# SensorInt.net
KiCad netlist of a schematic drawn in Altium Designer
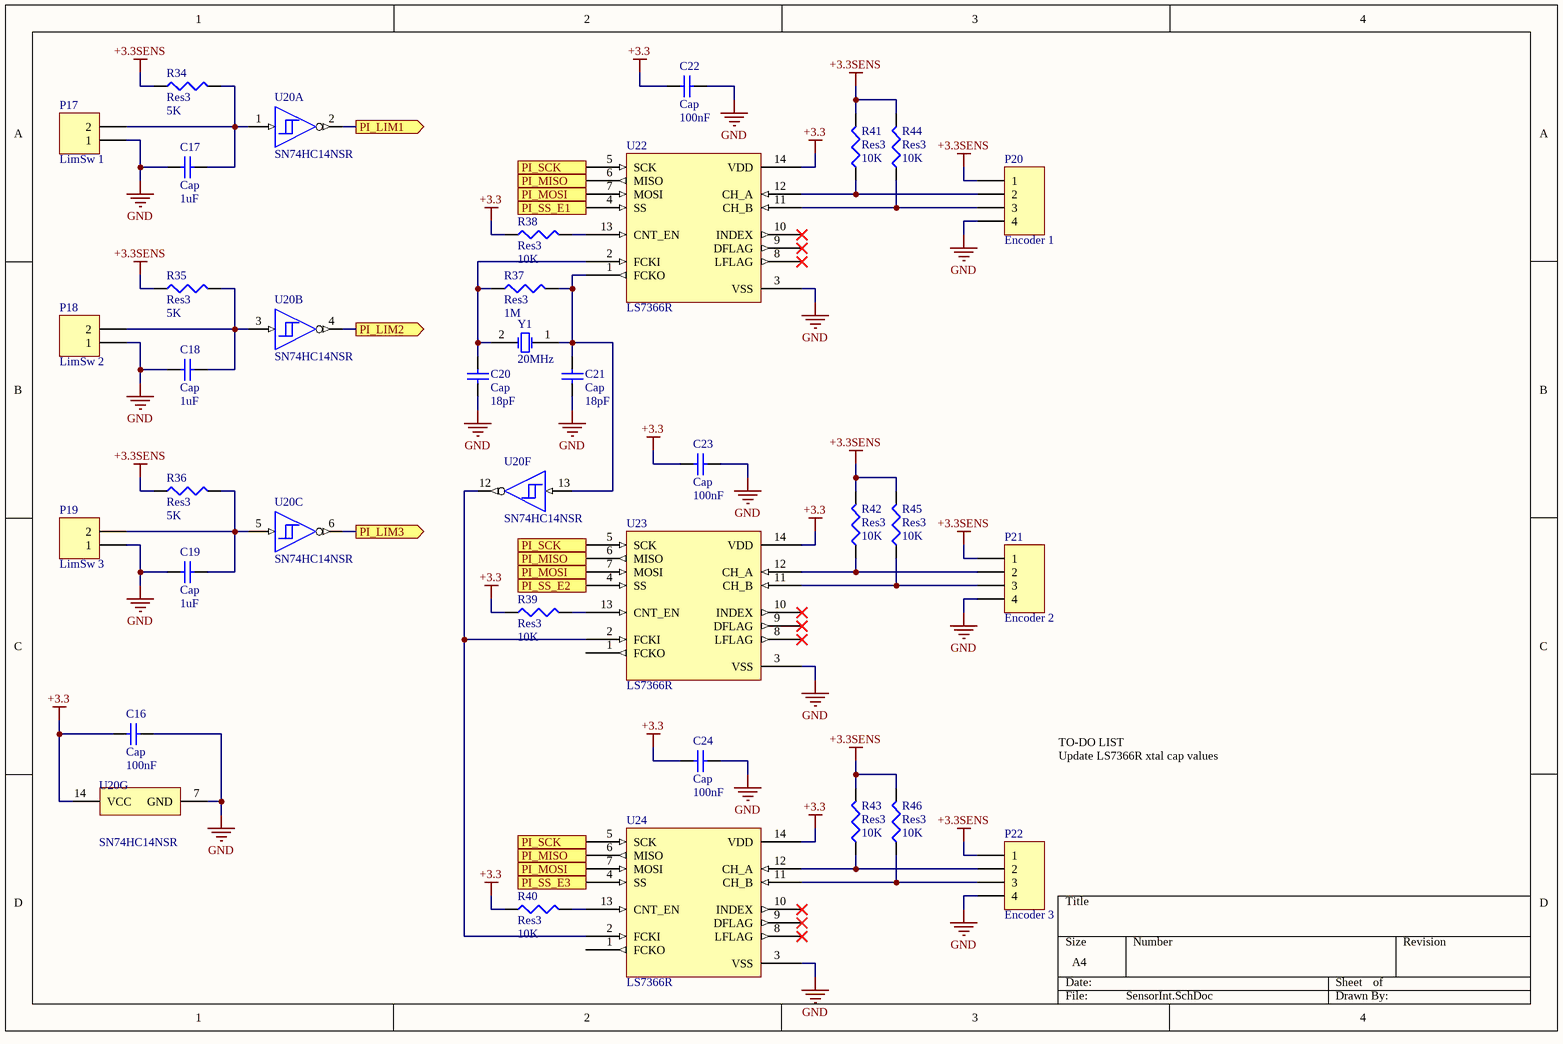
[diagram p0: SensorInt.SchDoc]

(export (version "E")
  (design (tool "Eeschema 10.0.6"))
  (components
    (comp (ref "C16")
      (value "Cap")
      (footprint "C0805")
      (description "Capacitor")
      (fields (field (name "ALTIUM_VALUE") "100nF") (field (name "PUBLISHER") "Altium Limited"))
      (libsource (lib "Miscellaneous Devices") (part "Cap"))
    )
    (comp (ref "C17")
      (value "Cap")
      (footprint "C0805")
      (description "Capacitor")
      (fields (field (name "ALTIUM_VALUE") "1uF") (field (name "PUBLISHER") "Altium Limited"))
      (libsource (lib "Miscellaneous Devices") (part "Cap"))
    )
    (comp (ref "C18")
      (value "Cap")
      (footprint "C0805")
      (description "Capacitor")
      (fields (field (name "ALTIUM_VALUE") "1uF") (field (name "PUBLISHER") "Altium Limited"))
      (libsource (lib "Miscellaneous Devices") (part "Cap"))
    )
    (comp (ref "C19")
      (value "Cap")
      (footprint "C0805")
      (description "Capacitor")
      (fields (field (name "ALTIUM_VALUE") "1uF") (field (name "PUBLISHER") "Altium Limited"))
      (libsource (lib "Miscellaneous Devices") (part "Cap"))
    )
    (comp (ref "C20")
      (value "Cap")
      (footprint "C0805")
      (description "Capacitor")
      (fields (field (name "ALTIUM_VALUE") "18pF") (field (name "PUBLISHER") "Altium Limited"))
      (libsource (lib "Miscellaneous Devices") (part "Cap"))
    )
    (comp (ref "C21")
      (value "Cap")
      (footprint "C0805")
      (description "Capacitor")
      (fields (field (name "ALTIUM_VALUE") "18pF") (field (name "PUBLISHER") "Altium Limited"))
      (libsource (lib "Miscellaneous Devices") (part "Cap"))
    )
    (comp (ref "C22")
      (value "Cap")
      (footprint "C0805")
      (description "Capacitor")
      (fields (field (name "ALTIUM_VALUE") "100nF") (field (name "PUBLISHER") "Altium Limited"))
      (libsource (lib "Miscellaneous Devices") (part "Cap"))
    )
    (comp (ref "C23")
      (value "Cap")
      (footprint "C0805")
      (description "Capacitor")
      (fields (field (name "ALTIUM_VALUE") "100nF") (field (name "PUBLISHER") "Altium Limited"))
      (libsource (lib "Miscellaneous Devices") (part "Cap"))
    )
    (comp (ref "C24")
      (value "Cap")
      (footprint "C0805")
      (description "Capacitor")
      (fields (field (name "ALTIUM_VALUE") "100nF") (field (name "PUBLISHER") "Altium Limited"))
      (libsource (lib "Miscellaneous Devices") (part "Cap"))
    )
    (comp (ref "P17")
      (value "LimSw 1")
      (footprint "22-23-20x1-2pos")
      (description "Header, 2-Pin")
      (fields (field (name "PUBLISHER") "Altium Limited"))
      (libsource (lib "Miscellaneous Connectors") (part "Header 2"))
    )
    (comp (ref "P18")
      (value "LimSw 2")
      (footprint "22-23-20x1-2pos")
      (description "Header, 2-Pin")
      (fields (field (name "PUBLISHER") "Altium Limited"))
      (libsource (lib "Miscellaneous Connectors") (part "Header 2"))
    )
    (comp (ref "P19")
      (value "LimSw 3")
      (footprint "22-23-20x1-2pos")
      (description "Header, 2-Pin")
      (fields (field (name "PUBLISHER") "Altium Limited"))
      (libsource (lib "Miscellaneous Connectors") (part "Header 2"))
    )
    (comp (ref "P20")
      (value "Encoder 1")
      (footprint "22-23-20x1-4pos")
      (description "Header, 4-Pin")
      (fields (field (name "PUBLISHER") "Altium Limited"))
      (libsource (lib "Miscellaneous Connectors") (part "Header 4"))
    )
    (comp (ref "P21")
      (value "Encoder 2")
      (footprint "22-23-20x1-4pos")
      (description "Header, 4-Pin")
      (fields (field (name "PUBLISHER") "Altium Limited"))
      (libsource (lib "Miscellaneous Connectors") (part "Header 4"))
    )
    (comp (ref "P22")
      (value "Encoder 3")
      (footprint "22-23-20x1-4pos")
      (description "Header, 4-Pin")
      (fields (field (name "PUBLISHER") "Altium Limited"))
      (libsource (lib "Miscellaneous Connectors") (part "Header 4"))
    )
    (comp (ref "R34")
      (value "Res3")
      (footprint "C0805")
      (description "Resistor")
      (fields (field (name "ALTIUM_VALUE") "5K") (field (name "PUBLISHER") "Altium Limited"))
      (libsource (lib "Miscellaneous Devices") (part "Res3"))
    )
    (comp (ref "R35")
      (value "Res3")
      (footprint "C0805")
      (description "Resistor")
      (fields (field (name "ALTIUM_VALUE") "5K") (field (name "PUBLISHER") "Altium Limited"))
      (libsource (lib "Miscellaneous Devices") (part "Res3"))
    )
    (comp (ref "R36")
      (value "Res3")
      (footprint "C0805")
      (description "Resistor")
      (fields (field (name "ALTIUM_VALUE") "5K") (field (name "PUBLISHER") "Altium Limited"))
      (libsource (lib "Miscellaneous Devices") (part "Res3"))
    )
    (comp (ref "R37")
      (value "Res3")
      (footprint "C0805")
      (description "Resistor")
      (fields (field (name "ALTIUM_VALUE") "1M") (field (name "PUBLISHER") "Altium Limited"))
      (libsource (lib "Miscellaneous Devices") (part "Res3"))
    )
    (comp (ref "R38")
      (value "Res3")
      (footprint "C0805")
      (description "Resistor")
      (fields (field (name "ALTIUM_VALUE") "10K") (field (name "PUBLISHER") "Altium Limited"))
      (libsource (lib "Miscellaneous Devices") (part "Res3"))
    )
    (comp (ref "R39")
      (value "Res3")
      (footprint "C0805")
      (description "Resistor")
      (fields (field (name "ALTIUM_VALUE") "10K") (field (name "PUBLISHER") "Altium Limited"))
      (libsource (lib "Miscellaneous Devices") (part "Res3"))
    )
    (comp (ref "R40")
      (value "Res3")
      (footprint "C0805")
      (description "Resistor")
      (fields (field (name "ALTIUM_VALUE") "10K") (field (name "PUBLISHER") "Altium Limited"))
      (libsource (lib "Miscellaneous Devices") (part "Res3"))
    )
    (comp (ref "R41")
      (value "Res3")
      (footprint "C0805")
      (description "Resistor")
      (fields (field (name "ALTIUM_VALUE") "10K") (field (name "PUBLISHER") "Altium Limited"))
      (libsource (lib "Miscellaneous Devices") (part "Res3"))
    )
    (comp (ref "R42")
      (value "Res3")
      (footprint "C0805")
      (description "Resistor")
      (fields (field (name "ALTIUM_VALUE") "10K") (field (name "PUBLISHER") "Altium Limited"))
      (libsource (lib "Miscellaneous Devices") (part "Res3"))
    )
    (comp (ref "R43")
      (value "Res3")
      (footprint "C0805")
      (description "Resistor")
      (fields (field (name "ALTIUM_VALUE") "10K") (field (name "PUBLISHER") "Altium Limited"))
      (libsource (lib "Miscellaneous Devices") (part "Res3"))
    )
    (comp (ref "R44")
      (value "Res3")
      (footprint "C0805")
      (description "Resistor")
      (fields (field (name "ALTIUM_VALUE") "10K") (field (name "PUBLISHER") "Altium Limited"))
      (libsource (lib "Miscellaneous Devices") (part "Res3"))
    )
    (comp (ref "R45")
      (value "Res3")
      (footprint "C0805")
      (description "Resistor")
      (fields (field (name "ALTIUM_VALUE") "10K") (field (name "PUBLISHER") "Altium Limited"))
      (libsource (lib "Miscellaneous Devices") (part "Res3"))
    )
    (comp (ref "R46")
      (value "Res3")
      (footprint "C0805")
      (description "Resistor")
      (fields (field (name "ALTIUM_VALUE") "10K") (field (name "PUBLISHER") "Altium Limited"))
      (libsource (lib "Miscellaneous Devices") (part "Res3"))
    )
    (comp (ref "U20")
      (value "SN74HC14NSR")
      (footprint "NS0014A_M")
      (description "Hex Schmitt-Trigger Inverters, NS0014A, LARGE T&R")
      (fields
        (field (name "GENERIC PART NUMBER") "SN74HC14")
        (field (name "MANUFACTURER") "Texas Instruments")
      )
      (libsource (lib "Altium Content Vault") (part "TI-CD_SNX4XXXXXX4X_19A-14-SCHMITT"))
    )
    (comp (ref "U22")
      (value "LS7366R")
      (footprint "SOIC14N")
      (description "32-BIT QUADRATURE COUNTER WITH SERIAL INTERFACE")
      (libsource (lib "ScienceSymbols") (part "LS7366R"))
    )
    (comp (ref "U23")
      (value "LS7366R")
      (footprint "SOIC14N")
      (description "32-BIT QUADRATURE COUNTER WITH SERIAL INTERFACE")
      (libsource (lib "ScienceSymbols") (part "LS7366R"))
    )
    (comp (ref "U24")
      (value "LS7366R")
      (footprint "SOIC14N")
      (description "32-BIT QUADRATURE COUNTER WITH SERIAL INTERFACE")
      (libsource (lib "ScienceSymbols") (part "LS7366R"))
    )
    (comp (ref "Y1")
      (value "20MHz")
      (footprint "ABM3")
      (description "Crystal Oscillator")
      (fields (field (name "PUBLISHER") "Altium Limited"))
      (libsource (lib "Miscellaneous Devices") (part "XTAL"))
    )
  )
  (nets
    (net (code "1") (name "+3.3") (class "Default")
      (node (ref "C16") (pin "1") (pinfunction "1_1") (pintype "passive"))
      (node (ref "C22") (pin "1") (pinfunction "1_1") (pintype "passive"))
      (node (ref "C23") (pin "1") (pinfunction "1_1") (pintype "passive"))
      (node (ref "C24") (pin "1") (pinfunction "1_1") (pintype "passive"))
      (node (ref "R38") (pin "1") (pinfunction "1_1") (pintype "passive"))
      (node (ref "R39") (pin "1") (pinfunction "1_1") (pintype "passive"))
      (node (ref "R40") (pin "1") (pinfunction "1_1") (pintype "passive"))
      (node (ref "U20") (pin "14") (pinfunction "VCC_14") (pintype "power_in"))
      (node (ref "U22") (pin "14") (pinfunction "VDD_14") (pintype "power_in"))
      (node (ref "U23") (pin "14") (pinfunction "VDD_14") (pintype "power_in"))
      (node (ref "U24") (pin "14") (pinfunction "VDD_14") (pintype "power_in"))
    )
    (net (code "2") (name "+3.3SENS") (class "Default")
      (node (ref "P20") (pin "1") (pinfunction "1_1") (pintype "passive"))
      (node (ref "P21") (pin "1") (pinfunction "1_1") (pintype "passive"))
      (node (ref "P22") (pin "1") (pinfunction "1_1") (pintype "passive"))
      (node (ref "R34") (pin "1") (pinfunction "1_1") (pintype "passive"))
      (node (ref "R35") (pin "1") (pinfunction "1_1") (pintype "passive"))
      (node (ref "R36") (pin "1") (pinfunction "1_1") (pintype "passive"))
      (node (ref "R41") (pin "2") (pinfunction "2_2") (pintype "passive"))
      (node (ref "R42") (pin "2") (pinfunction "2_2") (pintype "passive"))
      (node (ref "R43") (pin "2") (pinfunction "2_2") (pintype "passive"))
      (node (ref "R44") (pin "2") (pinfunction "2_2") (pintype "passive"))
      (node (ref "R45") (pin "2") (pinfunction "2_2") (pintype "passive"))
      (node (ref "R46") (pin "2") (pinfunction "2_2") (pintype "passive"))
    )
    (net (code "3") (name "/PI_LIM1") (class "Default")
      (node (ref "U20") (pin "2") (pinfunction "~{1Y}_2") (pintype "output"))
    )
    (net (code "4") (name "/PI_LIM2") (class "Default")
      (node (ref "U20") (pin "4") (pinfunction "~{2Y}_4") (pintype "output"))
    )
    (net (code "5") (name "/PI_LIM3") (class "Default")
      (node (ref "U20") (pin "6") (pinfunction "~{3Y}_6") (pintype "output"))
    )
    (net (code "6") (name "/PI_MISO") (class "Default")
      (node (ref "U22") (pin "6") (pinfunction "MISO_6") (pintype "output"))
      (node (ref "U23") (pin "6") (pinfunction "MISO_6") (pintype "output"))
      (node (ref "U24") (pin "6") (pinfunction "MISO_6") (pintype "output"))
    )
    (net (code "7") (name "/PI_MOSI") (class "Default")
      (node (ref "U22") (pin "7") (pinfunction "MOSI_7") (pintype "input"))
      (node (ref "U23") (pin "7") (pinfunction "MOSI_7") (pintype "input"))
      (node (ref "U24") (pin "7") (pinfunction "MOSI_7") (pintype "input"))
    )
    (net (code "8") (name "/PI_SCK") (class "Default")
      (node (ref "U22") (pin "5") (pinfunction "SCK_5") (pintype "input"))
      (node (ref "U23") (pin "5") (pinfunction "SCK_5") (pintype "input"))
      (node (ref "U24") (pin "5") (pinfunction "SCK_5") (pintype "input"))
    )
    (net (code "9") (name "/PI_SS_E1") (class "Default")
      (node (ref "U22") (pin "4") (pinfunction "SS_4") (pintype "input"))
    )
    (net (code "10") (name "/PI_SS_E2") (class "Default")
      (node (ref "U23") (pin "4") (pinfunction "SS_4") (pintype "input"))
    )
    (net (code "11") (name "/PI_SS_E3") (class "Default")
      (node (ref "U24") (pin "4") (pinfunction "SS_4") (pintype "input"))
    )
    (net (code "12") (name "GND") (class "Default")
      (node (ref "C16") (pin "2") (pinfunction "2_2") (pintype "passive"))
      (node (ref "C17") (pin "1") (pinfunction "1_1") (pintype "passive"))
      (node (ref "C18") (pin "1") (pinfunction "1_1") (pintype "passive"))
      (node (ref "C19") (pin "1") (pinfunction "1_1") (pintype "passive"))
      (node (ref "C20") (pin "1") (pinfunction "1_1") (pintype "passive"))
      (node (ref "C21") (pin "1") (pinfunction "1_1") (pintype "passive"))
      (node (ref "C22") (pin "2") (pinfunction "2_2") (pintype "passive"))
      (node (ref "C23") (pin "2") (pinfunction "2_2") (pintype "passive"))
      (node (ref "C24") (pin "2") (pinfunction "2_2") (pintype "passive"))
      (node (ref "P17") (pin "1") (pinfunction "1_1") (pintype "passive"))
      (node (ref "P18") (pin "1") (pinfunction "1_1") (pintype "passive"))
      (node (ref "P19") (pin "1") (pinfunction "1_1") (pintype "passive"))
      (node (ref "P20") (pin "4") (pinfunction "4_4") (pintype "passive"))
      (node (ref "P21") (pin "4") (pinfunction "4_4") (pintype "passive"))
      (node (ref "P22") (pin "4") (pinfunction "4_4") (pintype "passive"))
      (node (ref "U20") (pin "7") (pinfunction "GND_7") (pintype "power_in"))
      (node (ref "U22") (pin "3") (pinfunction "VSS_3") (pintype "power_in"))
      (node (ref "U23") (pin "3") (pinfunction "VSS_3") (pintype "power_in"))
      (node (ref "U24") (pin "3") (pinfunction "VSS_3") (pintype "power_in"))
    )
    (net (code "13") (name "Net-(U20A-1A)") (class "Default")
      (node (ref "C17") (pin "2") (pinfunction "2_2") (pintype "passive"))
      (node (ref "P17") (pin "2") (pinfunction "2_2") (pintype "passive"))
      (node (ref "R34") (pin "2") (pinfunction "2_2") (pintype "passive"))
      (node (ref "U20") (pin "1") (pinfunction "1A_1") (pintype "input"))
    )
    (net (code "14") (name "Net-(U20B-2A)") (class "Default")
      (node (ref "C18") (pin "2") (pinfunction "2_2") (pintype "passive"))
      (node (ref "P18") (pin "2") (pinfunction "2_2") (pintype "passive"))
      (node (ref "R35") (pin "2") (pinfunction "2_2") (pintype "passive"))
      (node (ref "U20") (pin "3") (pinfunction "2A_3") (pintype "input"))
    )
    (net (code "15") (name "Net-(U20C-3A)") (class "Default")
      (node (ref "C19") (pin "2") (pinfunction "2_2") (pintype "passive"))
      (node (ref "P19") (pin "2") (pinfunction "2_2") (pintype "passive"))
      (node (ref "R36") (pin "2") (pinfunction "2_2") (pintype "passive"))
      (node (ref "U20") (pin "5") (pinfunction "3A_5") (pintype "input"))
    )
    (net (code "16") (name "Net-(U20F-6A)") (class "Default")
      (node (ref "C21") (pin "2") (pinfunction "2_2") (pintype "passive"))
      (node (ref "R37") (pin "2") (pinfunction "2_2") (pintype "passive"))
      (node (ref "U20") (pin "13") (pinfunction "6A_13") (pintype "input"))
      (node (ref "U22") (pin "1") (pinfunction "FCKO_1") (pintype "output"))
      (node (ref "Y1") (pin "1") (pinfunction "OSC1_1") (pintype "passive"))
    )
    (net (code "17") (name "Net-(U20F-~{6Y})") (class "Default")
      (node (ref "U20") (pin "12") (pinfunction "~{6Y}_12") (pintype "output"))
      (node (ref "U23") (pin "2") (pinfunction "FCKI_2") (pintype "input"))
      (node (ref "U24") (pin "2") (pinfunction "FCKI_2") (pintype "input"))
    )
    (net (code "18") (name "Net-(U22-CH_A)") (class "Default")
      (node (ref "P20") (pin "2") (pinfunction "2_2") (pintype "passive"))
      (node (ref "R41") (pin "1") (pinfunction "1_1") (pintype "passive"))
      (node (ref "U22") (pin "12") (pinfunction "CH_A_12") (pintype "input"))
    )
    (net (code "19") (name "Net-(U22-CH_B)") (class "Default")
      (node (ref "P20") (pin "3") (pinfunction "3_3") (pintype "passive"))
      (node (ref "R44") (pin "1") (pinfunction "1_1") (pintype "passive"))
      (node (ref "U22") (pin "11") (pinfunction "CH_B_11") (pintype "input"))
    )
    (net (code "20") (name "Net-(U22-CNT_EN)") (class "Default")
      (node (ref "R38") (pin "2") (pinfunction "2_2") (pintype "passive"))
      (node (ref "U22") (pin "13") (pinfunction "CNT_EN_13") (pintype "input"))
    )
    (net (code "21") (name "Net-(U22-FCKI)") (class "Default")
      (node (ref "C20") (pin "2") (pinfunction "2_2") (pintype "passive"))
      (node (ref "R37") (pin "1") (pinfunction "1_1") (pintype "passive"))
      (node (ref "U22") (pin "2") (pinfunction "FCKI_2") (pintype "input"))
      (node (ref "Y1") (pin "2") (pinfunction "OSC2_2") (pintype "passive"))
    )
    (net (code "22") (name "Net-(U23-CH_A)") (class "Default")
      (node (ref "P21") (pin "2") (pinfunction "2_2") (pintype "passive"))
      (node (ref "R42") (pin "1") (pinfunction "1_1") (pintype "passive"))
      (node (ref "U23") (pin "12") (pinfunction "CH_A_12") (pintype "input"))
    )
    (net (code "23") (name "Net-(U23-CH_B)") (class "Default")
      (node (ref "P21") (pin "3") (pinfunction "3_3") (pintype "passive"))
      (node (ref "R45") (pin "1") (pinfunction "1_1") (pintype "passive"))
      (node (ref "U23") (pin "11") (pinfunction "CH_B_11") (pintype "input"))
    )
    (net (code "24") (name "Net-(U23-CNT_EN)") (class "Default")
      (node (ref "R39") (pin "2") (pinfunction "2_2") (pintype "passive"))
      (node (ref "U23") (pin "13") (pinfunction "CNT_EN_13") (pintype "input"))
    )
    (net (code "25") (name "Net-(U24-CH_A)") (class "Default")
      (node (ref "P22") (pin "2") (pinfunction "2_2") (pintype "passive"))
      (node (ref "R43") (pin "1") (pinfunction "1_1") (pintype "passive"))
      (node (ref "U24") (pin "12") (pinfunction "CH_A_12") (pintype "input"))
    )
    (net (code "26") (name "Net-(U24-CH_B)") (class "Default")
      (node (ref "P22") (pin "3") (pinfunction "3_3") (pintype "passive"))
      (node (ref "R46") (pin "1") (pinfunction "1_1") (pintype "passive"))
      (node (ref "U24") (pin "11") (pinfunction "CH_B_11") (pintype "input"))
    )
    (net (code "27") (name "Net-(U24-CNT_EN)") (class "Default")
      (node (ref "R40") (pin "2") (pinfunction "2_2") (pintype "passive"))
      (node (ref "U24") (pin "13") (pinfunction "CNT_EN_13") (pintype "input"))
    )
    (net (code "28") (name "unconnected-(U22-DFLAG-Pad9)") (class "Default")
      (node (ref "U22") (pin "9") (pinfunction "DFLAG_9") (pintype "output+no_connect"))
    )
    (net (code "29") (name "unconnected-(U22-INDEX-Pad10)") (class "Default")
      (node (ref "U22") (pin "10") (pinfunction "INDEX_10") (pintype "output+no_connect"))
    )
    (net (code "30") (name "unconnected-(U22-LFLAG-Pad8)") (class "Default")
      (node (ref "U22") (pin "8") (pinfunction "LFLAG_8") (pintype "output+no_connect"))
    )
    (net (code "31") (name "unconnected-(U23-DFLAG-Pad9)") (class "Default")
      (node (ref "U23") (pin "9") (pinfunction "DFLAG_9") (pintype "output+no_connect"))
    )
    (net (code "32") (name "unconnected-(U23-FCKO-Pad1)") (class "Default")
      (node (ref "U23") (pin "1") (pinfunction "FCKO_1") (pintype "output"))
    )
    (net (code "33") (name "unconnected-(U23-INDEX-Pad10)") (class "Default")
      (node (ref "U23") (pin "10") (pinfunction "INDEX_10") (pintype "output+no_connect"))
    )
    (net (code "34") (name "unconnected-(U23-LFLAG-Pad8)") (class "Default")
      (node (ref "U23") (pin "8") (pinfunction "LFLAG_8") (pintype "output+no_connect"))
    )
    (net (code "35") (name "unconnected-(U24-DFLAG-Pad9)") (class "Default")
      (node (ref "U24") (pin "9") (pinfunction "DFLAG_9") (pintype "output+no_connect"))
    )
    (net (code "36") (name "unconnected-(U24-FCKO-Pad1)") (class "Default")
      (node (ref "U24") (pin "1") (pinfunction "FCKO_1") (pintype "output"))
    )
    (net (code "37") (name "unconnected-(U24-INDEX-Pad10)") (class "Default")
      (node (ref "U24") (pin "10") (pinfunction "INDEX_10") (pintype "output+no_connect"))
    )
    (net (code "38") (name "unconnected-(U24-LFLAG-Pad8)") (class "Default")
      (node (ref "U24") (pin "8") (pinfunction "LFLAG_8") (pintype "output+no_connect"))
    )
  )
)
